# DC.net
KiCad netlist of a schematic drawn in Altium Designer
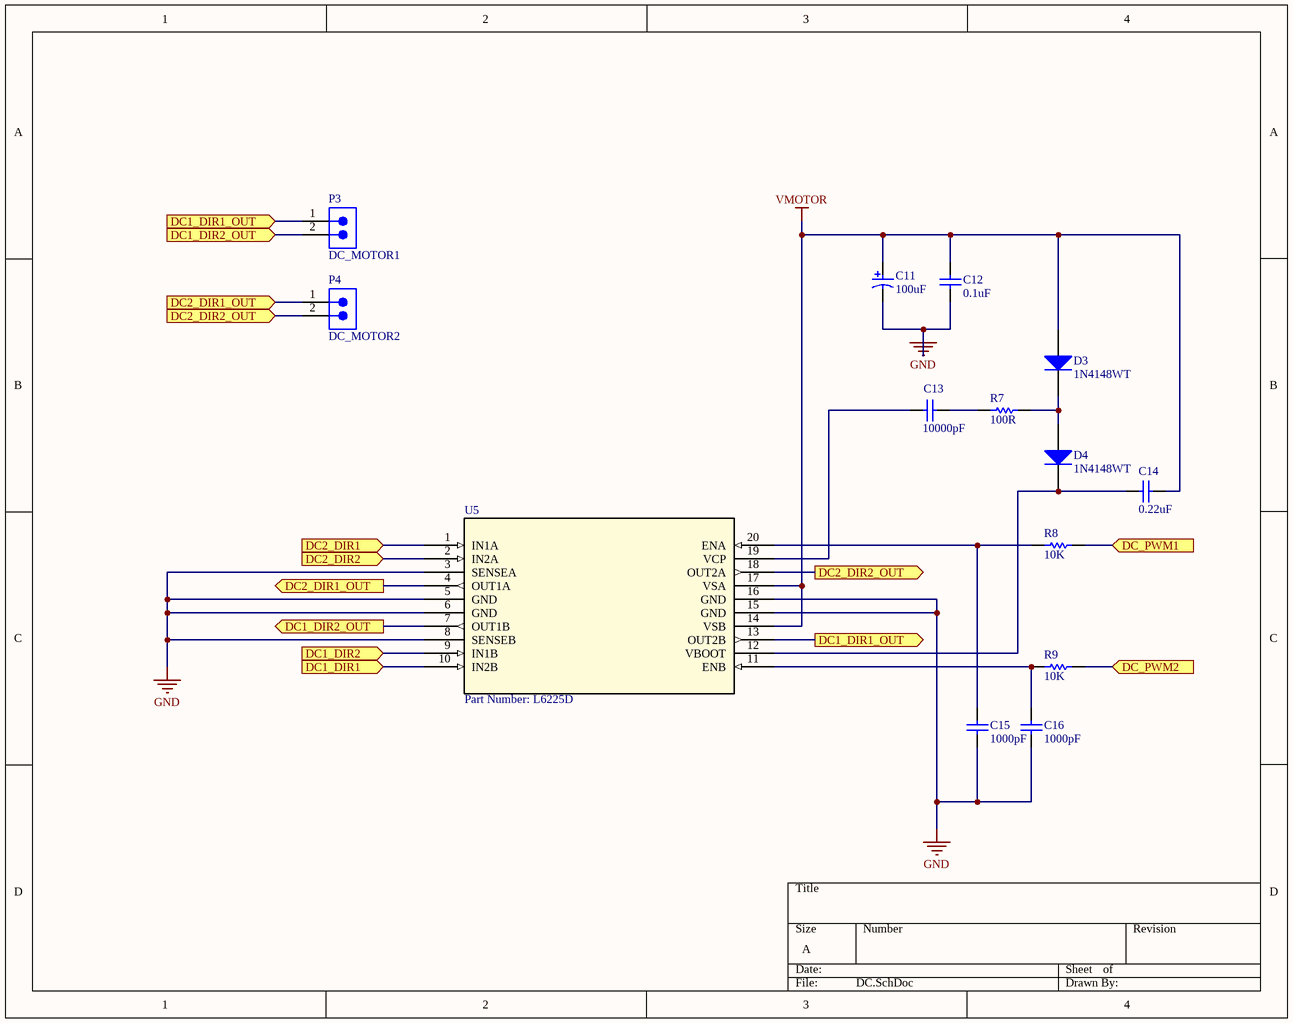
[diagram p0: DC.SchDoc]

(export (version "E")
  (design (tool "Eeschema 10.0.6"))
  (components
    (comp (ref "C11")
      (value "100uF")
      (footprint "NIC-CAPA2-6.3X5.8_V")
      (fields (field (name "PARTNUMBER") "UUD1C101MCL1GS") (field (name "MANUFACTURER") "Nichicon"))
      (libsource (lib "Altium Content Vault") (part "NIC-CAP-P-2"))
    )
    (comp (ref "C12")
      (value "0.1uF")
      (footprint "CAPC1608X90X35LL15T15")
      (description "Chip Capacitor, 100 nF, +/- 10%, 50 V, -55 to 125 degC, 0603 (1608 Metric), RoHS, Tape and Reel")
      (fields (field (name "TOLERANCE") "10%"))
      (libsource (lib "Altium Content Vault") (part "CAP-NP-2"))
    )
    (comp (ref "C13")
      (value "10000pF")
      (footprint "CAPC1608X90X35LL15T15")
      (fields
        (field (name "MANUFACTURER") "AVX Interconnect / Elco")
        (field (name "PART NUMBER") "06035C-103KAT2A")
      )
      (libsource (lib "Altium Content Vault") (part "CAP"))
    )
    (comp (ref "C14")
      (value "0.22uF")
      (footprint "CAPC1608X90X35ML10T15")
      (fields (field (name "MANUFACTURER") "Murata") (field (name "PART NUMBER") "GRM188F51H224ZA01D"))
      (libsource (lib "Altium Content Vault") (part "CAP"))
    )
    (comp (ref "C15")
      (value "1000pF")
      (footprint "CAPC2013X140X50NL20T25")
      (fields
        (field (name "MANUFACTURER") "AVX Interconnect / Elco")
        (field (name "PART NUMBER") "08051A102JAT2A")
      )
      (libsource (lib "Altium Content Vault") (part "CAP"))
    )
    (comp (ref "C16")
      (value "1000pF")
      (footprint "CAPC2013X140X50NL20T25")
      (fields
        (field (name "MANUFACTURER") "AVX Interconnect / Elco")
        (field (name "PART NUMBER") "08051A102JAT2A")
      )
      (libsource (lib "Altium Content Vault") (part "CAP"))
    )
    (comp (ref "D3")
      (value "1N4148WT")
      (footprint "FAIR-SOD-523F-2_V")
      (description "High Conductance Fast Switching Diode, 75 V, -55 to 150 degC, 2-Pin SOD523F, RoHS")
      (fields (field (name "MANUFACTURER") "Fairchild Semiconductor"))
      (libsource (lib "Altium Content Vault") (part "FAIR-D_K1A2-2"))
    )
    (comp (ref "D4")
      (value "1N4148WT")
      (footprint "FAIR-SOD-523F-2_V")
      (description "High Conductance Fast Switching Diode, 75 V, -55 to 150 degC, 2-Pin SOD523F, RoHS")
      (fields (field (name "MANUFACTURER") "Fairchild Semiconductor"))
      (libsource (lib "Altium Content Vault") (part "FAIR-D_K1A2-2"))
    )
    (comp (ref "P3")
      (value "DC_MOTOR1")
      (footprint "SMTC-DW-02-16-X-S-200")
      (fields (field (name "PARTNUMBER") "DW-02-16-G-S-200") (field (name "MANUFACTURER") "Samtec"))
      (libsource (lib "Altium Content Vault") (part "SMTC-DW-02-16-X-S-200"))
    )
    (comp (ref "P4")
      (value "DC_MOTOR2")
      (footprint "SMTC-DW-02-16-X-S-200")
      (fields (field (name "PARTNUMBER") "DW-02-16-G-S-200") (field (name "MANUFACTURER") "Samtec"))
      (libsource (lib "Altium Content Vault") (part "SMTC-DW-02-16-X-S-200"))
    )
    (comp (ref "R7")
      (value "100R")
      (footprint "RESC1609X50X30ML10T20")
      (fields (field (name "PART NUMBER") "CRCW0603100RJNEA") (field (name "MANUFACTURER") "Vishay Dale"))
      (libsource (lib "Altium Content Vault") (part "RES"))
    )
    (comp (ref "R8")
      (value "10K")
      (footprint "RESC1609X50X30ML10T20")
      (fields (field (name "MANUFACTURER") "Vishay Dale") (field (name "PART NUMBER") "CRCW060310K0JNEA"))
      (libsource (lib "Altium Content Vault") (part "RES"))
    )
    (comp (ref "R9")
      (value "10K")
      (footprint "RESC1609X50X30ML10T20")
      (fields (field (name "MANUFACTURER") "Vishay Dale") (field (name "PART NUMBER") "CRCW060310K0JNEA"))
      (libsource (lib "Altium Content Vault") (part "RES"))
    )
    (comp (ref "U5")
      (value "Part Number: L6225D")
      (footprint "SO-20")
      (description "No Description Available")
      (fields
        (field (name "MANUFACTURER_PART_NUMBER") "L6225D")
        (field (name "COPYRIGHT") "Copyright (C) 2018 Accelerated Designs. All rights reserved")
      )
      (libsource (lib "L6225D") (part "L6225D"))
    )
  )
  (nets
    (net (code "1") (name "/DC1_DIR1") (class "Default")
      (node (ref "U5") (pin "10") (pinfunction "IN2B_10") (pintype "input"))
    )
    (net (code "2") (name "/DC1_DIR1_OUT") (class "Default")
      (node (ref "P3") (pin "1") (pinfunction "1_1") (pintype "passive"))
      (node (ref "U5") (pin "13") (pinfunction "OUT2B_13") (pintype "output"))
    )
    (net (code "3") (name "/DC1_DIR2") (class "Default")
      (node (ref "U5") (pin "9") (pinfunction "IN1B_9") (pintype "input"))
    )
    (net (code "4") (name "/DC1_DIR2_OUT") (class "Default")
      (node (ref "P3") (pin "2") (pinfunction "2_2") (pintype "passive"))
      (node (ref "U5") (pin "7") (pinfunction "OUT1B_7") (pintype "output"))
    )
    (net (code "5") (name "/DC2_DIR1") (class "Default")
      (node (ref "U5") (pin "1") (pinfunction "IN1A_1") (pintype "input"))
    )
    (net (code "6") (name "/DC2_DIR1_OUT") (class "Default")
      (node (ref "P4") (pin "1") (pinfunction "1_1") (pintype "passive"))
      (node (ref "U5") (pin "4") (pinfunction "OUT1A_4") (pintype "output"))
    )
    (net (code "7") (name "/DC2_DIR2") (class "Default")
      (node (ref "U5") (pin "2") (pinfunction "IN2A_2") (pintype "input"))
    )
    (net (code "8") (name "/DC2_DIR2_OUT") (class "Default")
      (node (ref "P4") (pin "2") (pinfunction "2_2") (pintype "passive"))
      (node (ref "U5") (pin "18") (pinfunction "OUT2A_18") (pintype "output"))
    )
    (net (code "9") (name "/DC_PWM1") (class "Default")
      (node (ref "R8") (pin "1") (pinfunction "1_1") (pintype "passive"))
    )
    (net (code "10") (name "/DC_PWM2") (class "Default")
      (node (ref "R9") (pin "1") (pinfunction "1_1") (pintype "passive"))
    )
    (net (code "11") (name "GND") (class "Default")
      (node (ref "C11") (pin "2") (pinfunction "2_2") (pintype "passive"))
      (node (ref "C12") (pin "1") (pinfunction "1_1") (pintype "passive"))
      (node (ref "C15") (pin "1") (pinfunction "1_1") (pintype "passive"))
      (node (ref "C16") (pin "1") (pinfunction "1_1") (pintype "passive"))
      (node (ref "U5") (pin "15") (pinfunction "GND_15") (pintype "passive"))
      (node (ref "U5") (pin "16") (pinfunction "GND_16") (pintype "passive"))
      (node (ref "U5") (pin "3") (pinfunction "SENSEA_3") (pintype "power_in"))
      (node (ref "U5") (pin "5") (pinfunction "GND_5") (pintype "passive"))
      (node (ref "U5") (pin "6") (pinfunction "GND_6") (pintype "passive"))
      (node (ref "U5") (pin "8") (pinfunction "SENSEB_8") (pintype "power_in"))
    )
    (net (code "12") (name "Net-(C13-Pad2)") (class "Default")
      (node (ref "C13") (pin "2") (pinfunction "2_2") (pintype "passive"))
      (node (ref "R7") (pin "1") (pinfunction "1_1") (pintype "passive"))
    )
    (net (code "13") (name "Net-(D3-K)") (class "Default")
      (node (ref "D3") (pin "1") (pinfunction "K_1") (pintype "passive"))
      (node (ref "D4") (pin "2") (pinfunction "A_2") (pintype "passive"))
      (node (ref "R7") (pin "2") (pinfunction "2_2") (pintype "passive"))
    )
    (net (code "14") (name "Net-(D4-K)") (class "Default")
      (node (ref "C14") (pin "1") (pinfunction "1_1") (pintype "passive"))
      (node (ref "D4") (pin "1") (pinfunction "K_1") (pintype "passive"))
      (node (ref "U5") (pin "12") (pinfunction "VBOOT_12") (pintype "power_in"))
    )
    (net (code "15") (name "Net-(U5-ENA)") (class "Default")
      (node (ref "C15") (pin "2") (pinfunction "2_2") (pintype "passive"))
      (node (ref "R8") (pin "2") (pinfunction "2_2") (pintype "passive"))
      (node (ref "U5") (pin "20") (pinfunction "ENA_20") (pintype "input"))
    )
    (net (code "16") (name "Net-(U5-ENB)") (class "Default")
      (node (ref "C16") (pin "2") (pinfunction "2_2") (pintype "passive"))
      (node (ref "R9") (pin "2") (pinfunction "2_2") (pintype "passive"))
      (node (ref "U5") (pin "11") (pinfunction "ENB_11") (pintype "input"))
    )
    (net (code "17") (name "Net-(U5-VCP)") (class "Default")
      (node (ref "C13") (pin "1") (pinfunction "1_1") (pintype "passive"))
      (node (ref "U5") (pin "19") (pinfunction "VCP_19") (pintype "power_in"))
    )
    (net (code "18") (name "VMOTOR") (class "Default")
      (node (ref "C11") (pin "1") (pinfunction "1_1") (pintype "passive"))
      (node (ref "C12") (pin "2") (pinfunction "2_2") (pintype "passive"))
      (node (ref "C14") (pin "2") (pinfunction "2_2") (pintype "passive"))
      (node (ref "D3") (pin "2") (pinfunction "A_2") (pintype "passive"))
      (node (ref "U5") (pin "14") (pinfunction "VSB_14") (pintype "power_in"))
      (node (ref "U5") (pin "17") (pinfunction "VSA_17") (pintype "power_in"))
    )
  )
)
